# Acoustics_Board_Pg_2.net
KiCad netlist of a schematic drawn in Altium Designer
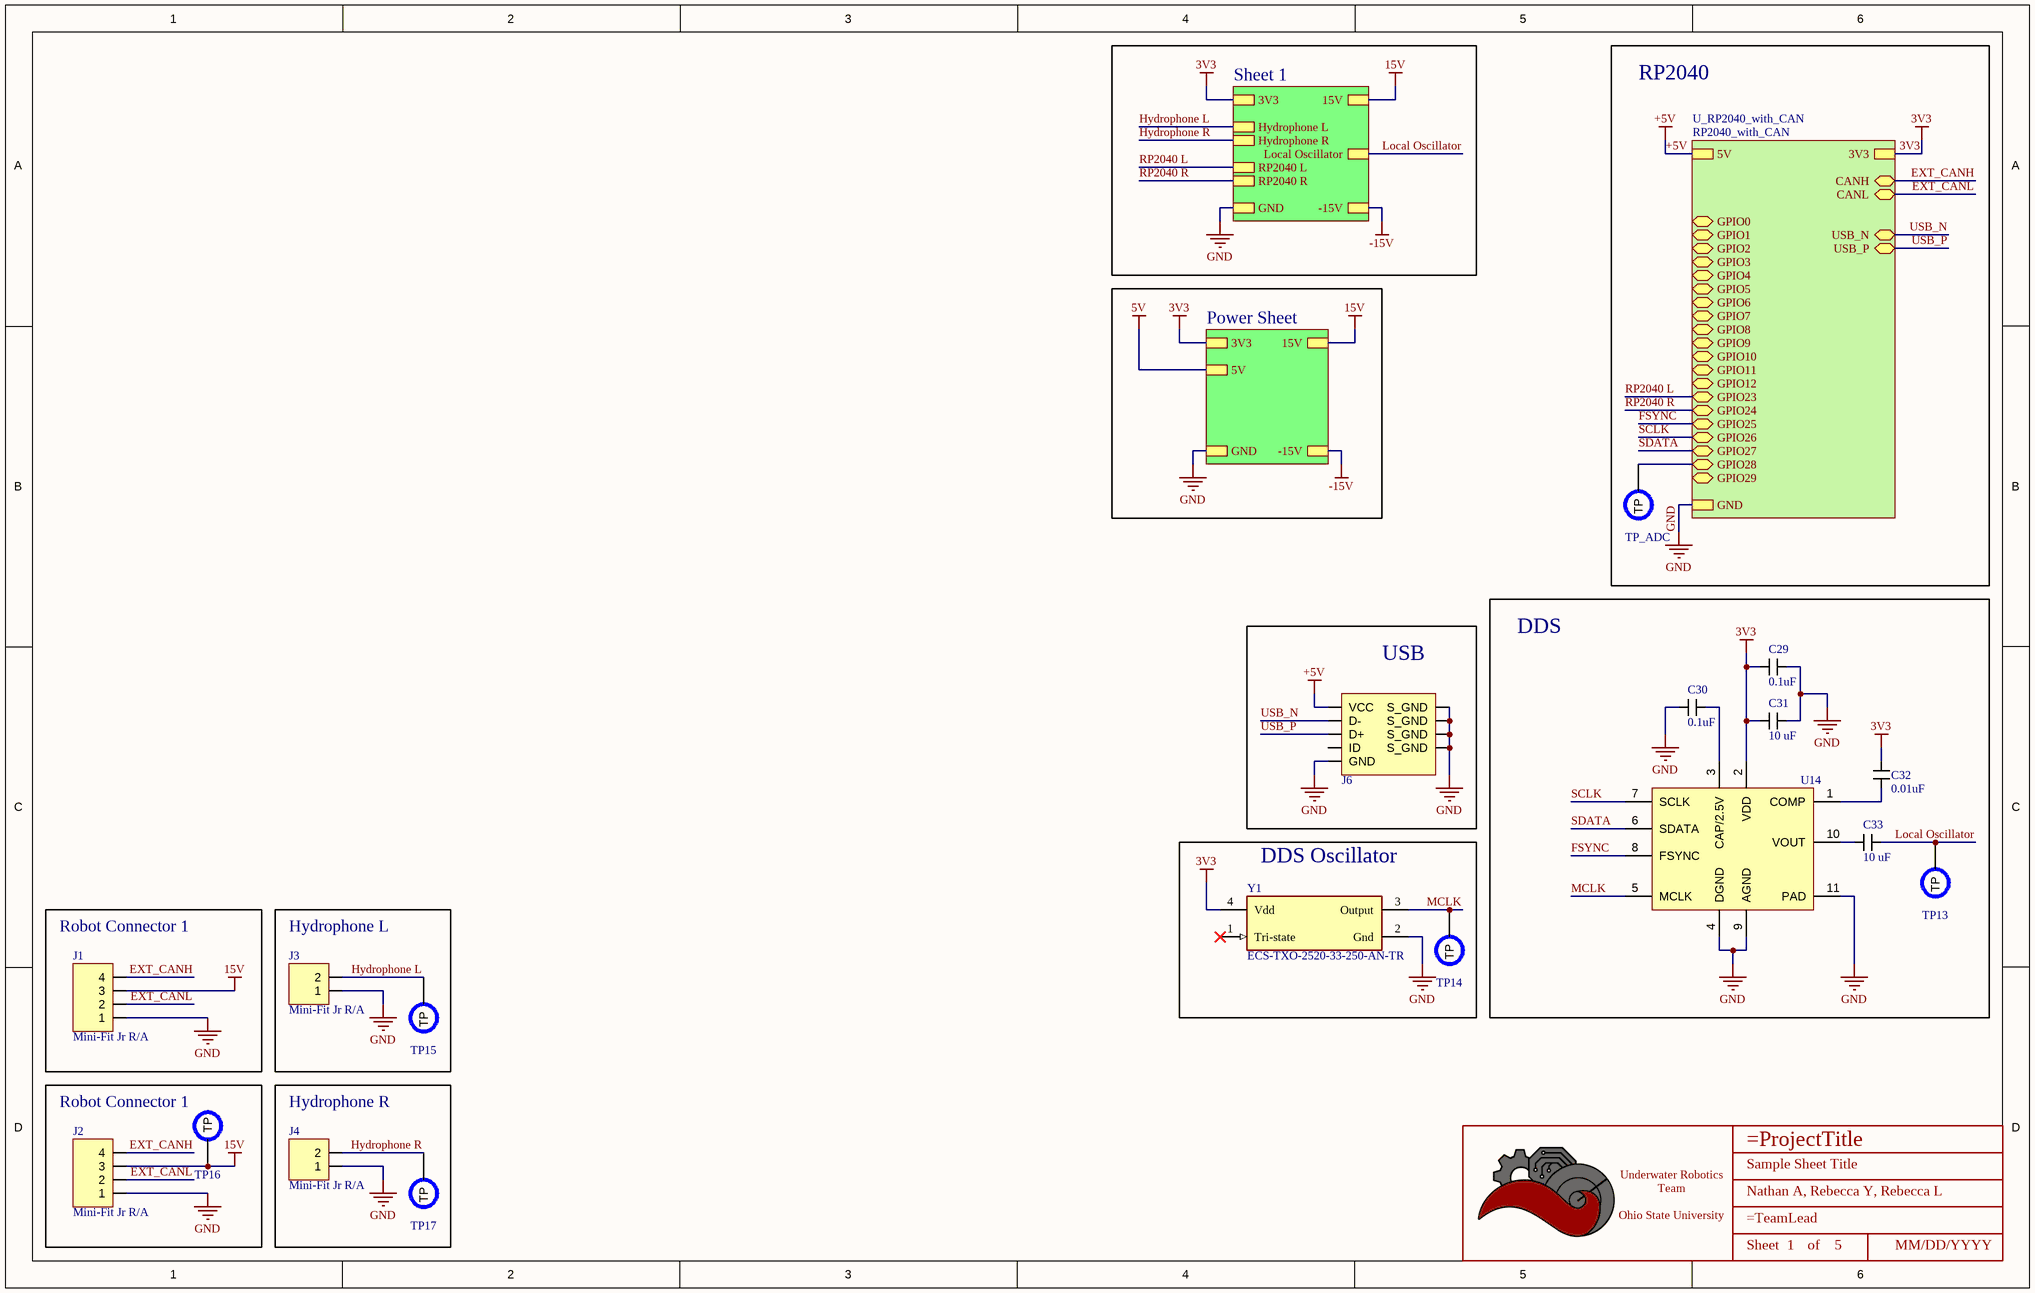
[diagram p0: Acoustics Board Pg. 2.SchDoc]

(export (version "E")
  (design (tool "Eeschema 10.0.6"))
  (components
    (comp (ref "*")
      (value "Title_Block")
      (footprint "LOGO")
      (description "UWRT Schematic Title Block Template\r\n\r\nCreated June 2021, Dylan Trainor")
      (libsource (lib "UWRT") (part "Title_Block"))
    )
    (comp (ref "C29")
      (value "0.1uF")
      (footprint "CAPACITOR_0603")
      (description "Cap 100nF 6.3V +/-10%\r\nCeramic 0603")
      (fields
        (field (name "TOLERANCE") "+/- 10%")
        (field (name "VOLTAGE") "6.3V")
        (field (name "MADE BY") "Flip B")
      )
      (libsource (lib "Capacitors") (part "CAPACITOR_0.1uF_0603"))
    )
    (comp (ref "C30")
      (value "0.1uF")
      (footprint "CAPACITOR_0603")
      (description "Cap 100nF 6.3V +/-10%\r\nCeramic 0603")
      (fields
        (field (name "TOLERANCE") "+/- 10%")
        (field (name "VOLTAGE") "6.3V")
        (field (name "MADE BY") "Flip B")
      )
      (libsource (lib "Capacitors") (part "CAPACITOR_0.1uF_0603"))
    )
    (comp (ref "C31")
      (value "10uF Ceramic 6.3V")
      (footprint "CAPACITOR_0603")
      (description "Cap 10uF 6.3V +/-20%\r\nCeramic 0603")
      (fields
        (field (name "TOLERANCE") "+/- 20%")
        (field (name "VOLTAGE") "6.3V")
        (field (name "VALUE (UF)") "10 uF")
        (field (name "MADE BY") "Flip B")
      )
      (libsource (lib "Capacitors") (part "CAPACITOR_10uF_0603"))
    )
    (comp (ref "C32")
      (value "0.01uF")
      (footprint "CAPACITOR_0603")
      (description "10000 pF ±10% 50V Ceramic Capacitor X7R 0603 (1608 Metric)")
      (fields
        (field (name "TOLERANCE") "+/- 10%")
        (field (name "VOLTAGE") "6.3V")
        (field (name "MADE BY") "Flip B")
      )
      (libsource (lib "Capacitors") (part "CAPACITOR_0.01uF_0603_50V"))
    )
    (comp (ref "C33")
      (value "10uF Ceramic 6.3V")
      (footprint "CAPACITOR_0603")
      (description "Cap 10uF 6.3V +/-20%\r\nCeramic 0603")
      (fields
        (field (name "TOLERANCE") "+/- 20%")
        (field (name "VOLTAGE") "6.3V")
        (field (name "VALUE (UF)") "10 uF")
        (field (name "MADE BY") "Flip B")
      )
      (libsource (lib "Capacitors") (part "CAPACITOR_10uF_0603"))
    )
    (comp (ref "J1")
      (value "Mini-Fit Jr R/A")
      (footprint "CONN_MOLEX_MINIFIT JR_4 POS_R/A")
      (description "Molex Minifit Jr. 5569 \r\n4 Pos R/A Natural")
      (fields (field (name "MANUFACTURER") "Molex") (field (name "CREATED BY") "Flip B"))
      (libsource (lib "Connectors") (part "CONN_MOLEX_MINIFIT JR_4POS_R/A"))
    )
    (comp (ref "J2")
      (value "Mini-Fit Jr R/A")
      (footprint "CONN_MOLEX_MINIFIT JR_4 POS_R/A")
      (description "Molex Minifit Jr. 5569 \r\n4 Pos R/A Natural")
      (fields (field (name "MANUFACTURER") "Molex") (field (name "CREATED BY") "Flip B"))
      (libsource (lib "Connectors") (part "CONN_MOLEX_MINIFIT JR_4POS_R/A"))
    )
    (comp (ref "J3")
      (value "Mini-Fit Jr R/A")
      (footprint "CONN_MOLEX_MINIFIT JR_2 POS_R/A")
      (description "Molex Minifit Jr. 5569 \r\n2 Pos R/A Natural")
      (fields (field (name "MANUFACTURER") "Molex") (field (name "CREATED BY") "Robert P"))
      (libsource (lib "Connectors") (part "CONN_MOLEX_MINIFIT JR_2POS_R/A"))
    )
    (comp (ref "J4")
      (value "Mini-Fit Jr R/A")
      (footprint "CONN_MOLEX_MINIFIT JR_2 POS_R/A")
      (description "Molex Minifit Jr. 5569 \r\n2 Pos R/A Natural")
      (fields (field (name "MANUFACTURER") "Molex") (field (name "CREATED BY") "Robert P"))
      (libsource (lib "Connectors") (part "CONN_MOLEX_MINIFIT JR_2POS_R/A"))
    )
    (comp (ref "J6")
      (value "USB_MICRO R/A")
      (footprint "CONN_MINIUSB")
      (description "Amphenol Micro USB-B\r\nUSB2.0 5 Pin Right Angle SMD")
      (fields (field (name "MANUFACTURER") "Amphenol") (field (name "CREATED BY") "Flip B"))
      (libsource (lib "Connectors") (part "CONN_MICROUSB"))
    )
    (comp (ref "TP13")
      (value "PCB Test Point")
      (footprint "TESTPOINT_1.2MM")
      (fields (field (name "MADE BY") "Robert Pafford"))
      (libsource (lib "Connectors") (part "TESTPOINT"))
    )
    (comp (ref "TP14")
      (value "PCB Test Point")
      (footprint "TESTPOINT_1.2MM")
      (fields (field (name "MADE BY") "Robert Pafford"))
      (libsource (lib "Connectors") (part "TESTPOINT"))
    )
    (comp (ref "TP15")
      (value "PCB Test Point")
      (footprint "TESTPOINT_1.2MM")
      (fields (field (name "MADE BY") "Robert Pafford"))
      (libsource (lib "Connectors") (part "TESTPOINT"))
    )
    (comp (ref "TP16")
      (value "PCB Test Point")
      (footprint "TESTPOINT_1.2MM")
      (fields (field (name "MADE BY") "Robert Pafford"))
      (libsource (lib "Connectors") (part "TESTPOINT"))
    )
    (comp (ref "TP17")
      (value "PCB Test Point")
      (footprint "TESTPOINT_1.2MM")
      (fields (field (name "MADE BY") "Robert Pafford"))
      (libsource (lib "Connectors") (part "TESTPOINT"))
    )
    (comp (ref "TP_ADC")
      (value "PCB Test Point")
      (footprint "TESTPOINT_1.2MM")
      (fields (field (name "MADE BY") "Robert Pafford"))
      (libsource (lib "Connectors") (part "TESTPOINT"))
    )
    (comp (ref "U14")
      (value "IC DDS 5MHZ 10BIT 10LFCSP")
      (footprint "CP-10-9")
      (description "Direct Digital Synthesis IC 10 b 5 MHz 28 b Tuning 10-LFCSP-WD (3x3)")
      (libsource (lib "Integrated Circuits") (part "AD9837ACPZ"))
    )
    (comp (ref "Y1")
      (value "ECS-TXO-2520-33-250-AN-TR")
      (footprint "FP-ECS-TXO-2520-MFG")
      (description "XTAL OSC TCXO 25.0000MHZ HCMOS")
      (libsource (lib "Altium Content Vault") (part "04cd953f3cf158082f8c09fbdb924ef"))
    )
  )
  (nets
    (net (code "1") (name "+5V") (class "Default")
      (node (ref "J6") (pin "1") (pinfunction "VCC_1") (pintype "passive"))
    )
    (net (code "3") (name "/EXT_CANH") (class "Default")
      (node (ref "J1") (pin "4") (pinfunction "4_4") (pintype "passive"))
      (node (ref "J2") (pin "4") (pinfunction "4_4") (pintype "passive"))
    )
    (net (code "4") (name "/EXT_CANL") (class "Default")
      (node (ref "J1") (pin "2") (pinfunction "2_2") (pintype "passive"))
      (node (ref "J2") (pin "2") (pinfunction "2_2") (pintype "passive"))
    )
    (net (code "5") (name "/FSYNC") (class "Default")
      (node (ref "U14") (pin "8") (pinfunction "FSYNC_8") (pintype "passive"))
    )
    (net (code "19") (name "/GPIO28") (class "Default")
      (node (ref "TP_ADC") (pin "TP") (pinfunction "TP_TP") (pintype "passive"))
    )
    (net (code "21") (name "/Hydrophone L") (class "Default")
      (node (ref "J3") (pin "2") (pinfunction "2_2") (pintype "passive"))
      (node (ref "TP15") (pin "TP") (pinfunction "TP_TP") (pintype "passive"))
    )
    (net (code "22") (name "/Hydrophone R") (class "Default")
      (node (ref "J4") (pin "2") (pinfunction "2_2") (pintype "passive"))
      (node (ref "TP17") (pin "TP") (pinfunction "TP_TP") (pintype "passive"))
    )
    (net (code "23") (name "/Local Oscillator") (class "Default")
      (node (ref "C33") (pin "2") (pinfunction "2_2") (pintype "passive"))
      (node (ref "TP13") (pin "TP") (pinfunction "TP_TP") (pintype "passive"))
    )
    (net (code "24") (name "/MCLK") (class "Default")
      (node (ref "TP14") (pin "TP") (pinfunction "TP_TP") (pintype "passive"))
      (node (ref "U14") (pin "5") (pinfunction "MCLK_5") (pintype "passive"))
      (node (ref "Y1") (pin "3") (pinfunction "Output_3") (pintype "tri_state"))
    )
    (net (code "27") (name "/SCLK") (class "Default")
      (node (ref "U14") (pin "7") (pinfunction "SCLK_7") (pintype "passive"))
    )
    (net (code "28") (name "/SDATA") (class "Default")
      (node (ref "U14") (pin "6") (pinfunction "SDATA_6") (pintype "passive"))
    )
    (net (code "29") (name "/USB_N") (class "Default")
      (node (ref "J6") (pin "2") (pinfunction "D-_2") (pintype "passive"))
    )
    (net (code "30") (name "/USB_P") (class "Default")
      (node (ref "J6") (pin "3") (pinfunction "D+_3") (pintype "passive"))
    )
    (net (code "31") (name "3V3") (class "Default")
      (node (ref "C29") (pin "2") (pinfunction "2_2") (pintype "passive"))
      (node (ref "C31") (pin "1") (pinfunction "1_1") (pintype "passive"))
      (node (ref "C32") (pin "1") (pinfunction "1_1") (pintype "passive"))
      (node (ref "U14") (pin "2") (pinfunction "VDD_2") (pintype "passive"))
      (node (ref "Y1") (pin "4") (pinfunction "Vdd_4") (pintype "power_in"))
    )
    (net (code "33") (name "15V") (class "Default")
      (node (ref "J1") (pin "3") (pinfunction "3_3") (pintype "passive"))
      (node (ref "J2") (pin "3") (pinfunction "3_3") (pintype "passive"))
      (node (ref "TP16") (pin "TP") (pinfunction "TP_TP") (pintype "passive"))
    )
    (net (code "34") (name "GND") (class "Default")
      (node (ref "C29") (pin "1") (pinfunction "1_1") (pintype "passive"))
      (node (ref "C30") (pin "1") (pinfunction "1_1") (pintype "passive"))
      (node (ref "C31") (pin "2") (pinfunction "2_2") (pintype "passive"))
      (node (ref "J1") (pin "1") (pinfunction "1_1") (pintype "passive"))
      (node (ref "J2") (pin "1") (pinfunction "1_1") (pintype "passive"))
      (node (ref "J3") (pin "1") (pinfunction "1_1") (pintype "passive"))
      (node (ref "J4") (pin "1") (pinfunction "1_1") (pintype "passive"))
      (node (ref "J6") (pin "5") (pinfunction "GND_5") (pintype "passive"))
      (node (ref "J6") (pin "6") (pinfunction "S_GND_6") (pintype "passive"))
      (node (ref "J6") (pin "7") (pinfunction "S_GND_7") (pintype "passive"))
      (node (ref "J6") (pin "8") (pinfunction "S_GND_8") (pintype "passive"))
      (node (ref "J6") (pin "9") (pinfunction "S_GND_9") (pintype "passive"))
      (node (ref "U14") (pin "11") (pinfunction "PAD_11") (pintype "passive"))
      (node (ref "U14") (pin "4") (pinfunction "DGND_4") (pintype "passive"))
      (node (ref "U14") (pin "9") (pinfunction "AGND_9") (pintype "passive"))
      (node (ref "Y1") (pin "2") (pinfunction "Gnd_2") (pintype "power_in"))
    )
    (net (code "35") (name "Net-(U14-CAP{slash}2.5V)") (class "Default")
      (node (ref "C30") (pin "2") (pinfunction "2_2") (pintype "passive"))
      (node (ref "U14") (pin "3") (pinfunction "CAP/2.5V_3") (pintype "passive"))
    )
    (net (code "36") (name "Net-(U14-COMP)") (class "Default")
      (node (ref "C32") (pin "2") (pinfunction "2_2") (pintype "passive"))
      (node (ref "U14") (pin "1") (pinfunction "COMP_1") (pintype "passive"))
    )
    (net (code "37") (name "Net-(U14-VOUT)") (class "Default")
      (node (ref "C33") (pin "1") (pinfunction "1_1") (pintype "passive"))
      (node (ref "U14") (pin "10") (pinfunction "VOUT_10") (pintype "passive"))
    )
    (net (code "38") (name "unconnected-(J6-ID-Pad4)") (class "Default")
      (node (ref "J6") (pin "4") (pinfunction "ID_4") (pintype "passive"))
    )
    (net (code "39") (name "unconnected-(Y1-Tri-state-Pad1)") (class "Default")
      (node (ref "Y1") (pin "1") (pinfunction "Tri-state_1") (pintype "input+no_connect"))
    )
  )
)
